# schematic.net
KiCad netlist of a schematic drawn in EasyEDA Pro
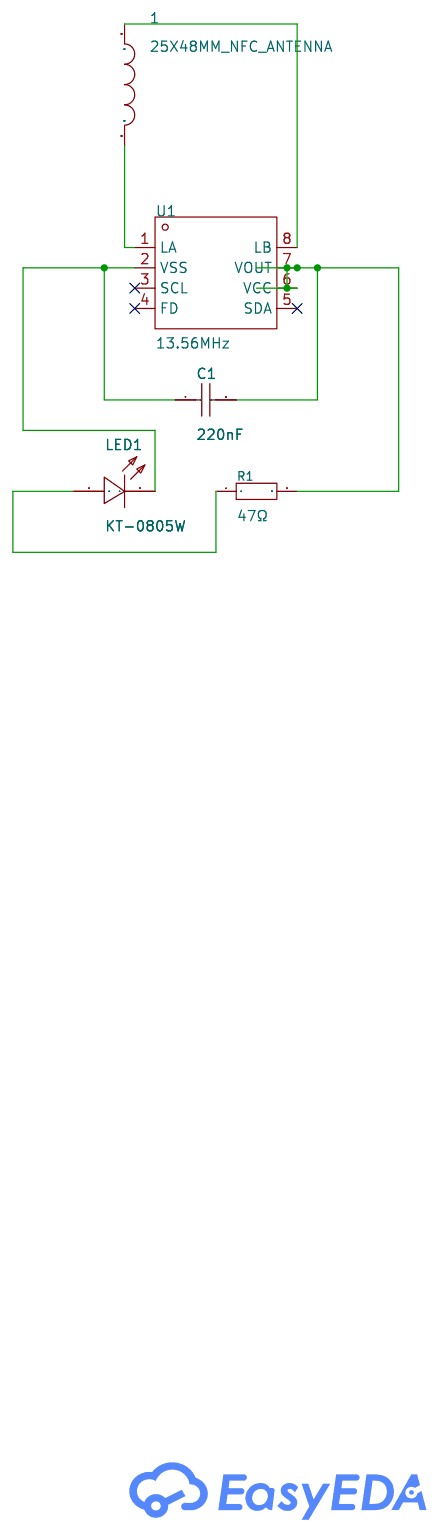
[diagram p0: schematic sheet]

(export (version "E")
  (design (tool "Eeschema 10.0.6"))
  (components
    (comp (ref "1") (value "25X48MM_NFC_ANTENNA") (libsource (lib "easyedapro") (part "25X48MM_NFC_ANTENNA")))
    (comp (ref "C1")
      (value "220nF")
      (footprint "easyedapro:C0603")
      (fields
        (field (name "Manufacturer Part") "CL10B224KA8NNNC")
        (field (name "Manufacturer") "SAMSUNG(三星)")
      )
      (libsource (lib "easyedapro") (part "CL10B224KA8NNNC"))
    )
    (comp (ref "LED1")
      (value "KT-0805W")
      (footprint "easyedapro:LED0805-R-RD")
      (fields (field (name "Manufacturer") "KENTO"))
      (libsource (lib "easyedapro") (part "whiteLEDSMD"))
    )
    (comp (ref "R1")
      (value "47Ω")
      (footprint "easyedapro:R0603")
      (fields
        (field (name "Manufacturer Part") "0603WAF470JT5E")
        (field (name "Manufacturer") "UNI-ROYAL(厚声)")
      )
      (libsource (lib "easyedapro") (part "0603WAF470JT5E"))
    )
    (comp (ref "U1")
      (value "13.56MHz")
      (footprint "easyedapro:XQFN-8_L1.6-W1.6-P0.50-BL_NT3H2111W0FHKH")
      (fields (field (name "Manufacturer Part") "NT3H2111W0FHKH") (field (name "Manufacturer") "NXP(恩智浦)"))
      (libsource (lib "easyedapro") (part "NT3H2111W0FHKH"))
    )
  )
  (nets
    (net (code "1") (name "Net-(LED1-A)") (class "Default")
      (node (ref "LED1") (pin "1") (pinfunction "A_1") (pintype "unspecified"))
      (node (ref "R1") (pin "1") (pinfunction "1_1") (pintype "input"))
    )
    (net (code "2") (name "Net-(LED1-K)") (class "Default")
      (node (ref "C1") (pin "1") (pinfunction "1_1") (pintype "input"))
      (node (ref "LED1") (pin "2") (pinfunction "K_2") (pintype "unspecified"))
      (node (ref "U1") (pin "2") (pinfunction "VSS_2") (pintype "unspecified"))
    )
    (net (code "3") (name "Net-(U1-LA)") (class "Default")
      (node (ref "1") (pin "P$2") (pinfunction "P$2_P$2") (pintype "bidirectional"))
      (node (ref "U1") (pin "1") (pinfunction "LA_1") (pintype "unspecified"))
    )
    (net (code "4") (name "Net-(U1-LB)") (class "Default")
      (node (ref "1") (pin "P$1") (pinfunction "P$1_P$1") (pintype "bidirectional"))
      (node (ref "U1") (pin "8") (pinfunction "LB_8") (pintype "unspecified"))
    )
    (net (code "5") (name "Net-(U1-VCC)") (class "Default")
      (node (ref "C1") (pin "2") (pinfunction "2_2") (pintype "input"))
      (node (ref "R1") (pin "2") (pinfunction "2_2") (pintype "input"))
      (node (ref "U1") (pin "6") (pinfunction "VCC_6") (pintype "unspecified"))
      (node (ref "U1") (pin "7") (pinfunction "VOUT_7") (pintype "unspecified"))
    )
    (net (code "6") (name "unconnected-(U1-FD-Pad4)") (class "Default")
      (node (ref "U1") (pin "4") (pinfunction "FD_4") (pintype "unspecified+no_connect"))
    )
    (net (code "7") (name "unconnected-(U1-SCL-Pad3)") (class "Default")
      (node (ref "U1") (pin "3") (pinfunction "SCL_3") (pintype "unspecified+no_connect"))
    )
    (net (code "8") (name "unconnected-(U1-SDA-Pad5)") (class "Default")
      (node (ref "U1") (pin "5") (pinfunction "SDA_5") (pintype "unspecified+no_connect"))
    )
  )
)
